# synergy-cart.net
KiCad netlist of a schematic drawn in EAGLE
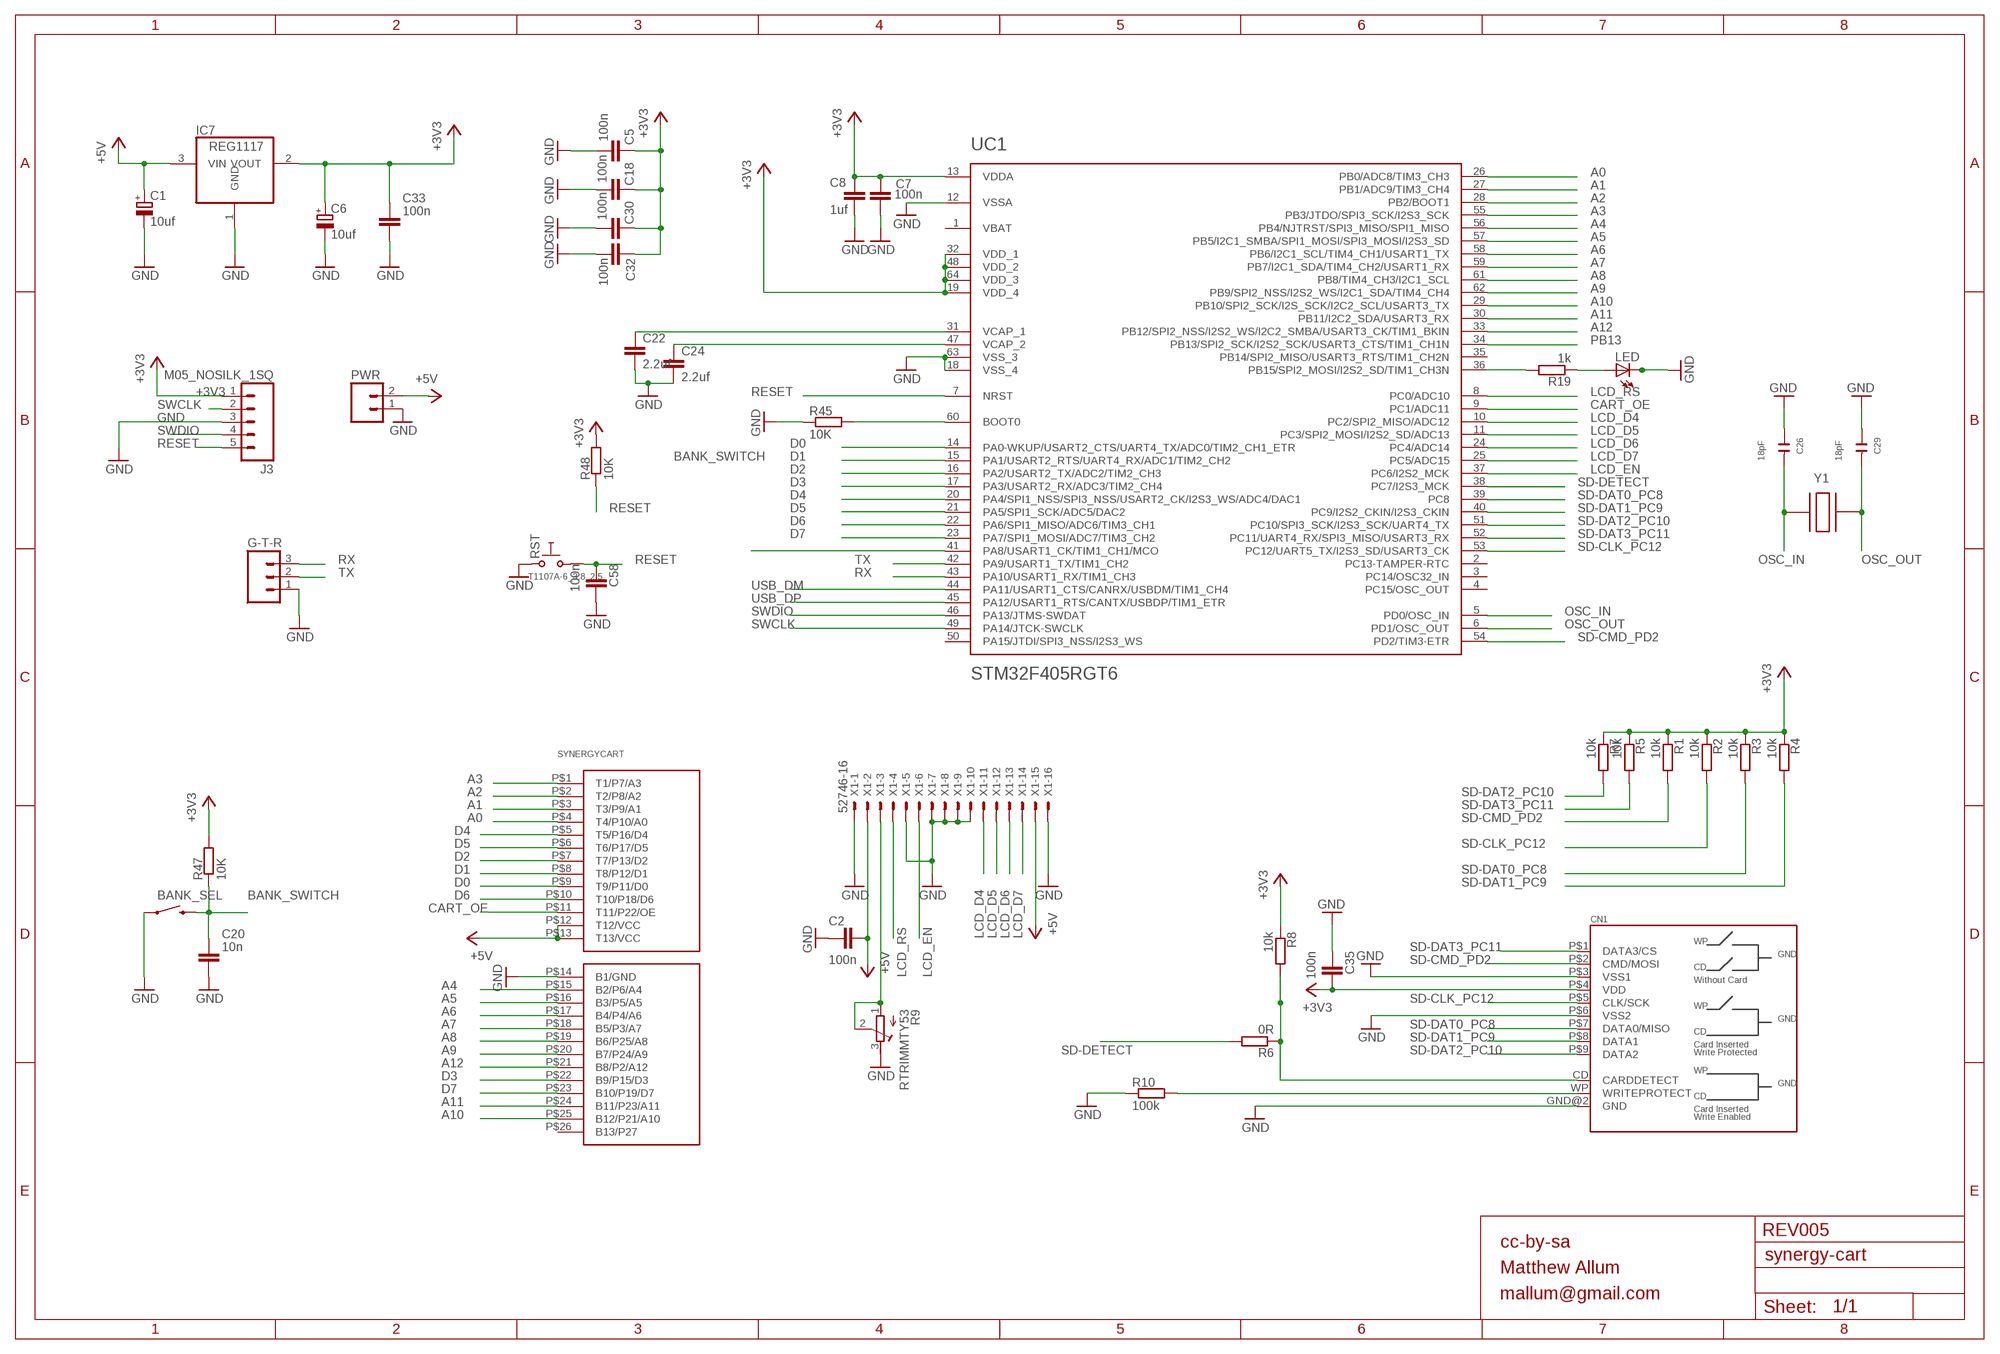
[diagram p0: schematic, sheet 1]

(export (version "E")
  (design (tool "Eeschema 10.0.6"))
  (components
    (comp (ref "BANK_SEL")
      (value "SWITCH-MOMENTARY-2PTH")
      (footprint "eagle-import:TACTILE-PTH")
      (libsource (lib "eagle-import") (part "SWITCH-MOMENTARY-2PTH"))
    )
    (comp (ref "C1")
      (value "10uf")
      (footprint "eagle-import:CT3216")
      (libsource (lib "eagle-import") (part "CAPACITOR_POLTANTALUM-CT3216"))
    )
    (comp (ref "C2")
      (value "100n")
      (footprint "eagle-import:C0603")
      (libsource (lib "eagle-import") (part "local_CAPACITOR0603"))
    )
    (comp (ref "C5")
      (value "100n")
      (footprint "eagle-import:C0603")
      (libsource (lib "eagle-import") (part "CAPACITOR0603"))
    )
    (comp (ref "C6")
      (value "10uf")
      (footprint "eagle-import:CT3216")
      (libsource (lib "eagle-import") (part "CAPACITOR_POLTANTALUM-CT3216"))
    )
    (comp (ref "C7")
      (value "100n")
      (footprint "eagle-import:C0603")
      (libsource (lib "eagle-import") (part "CAPACITOR0603"))
    )
    (comp (ref "C8")
      (value "1uf")
      (footprint "eagle-import:C0603")
      (libsource (lib "eagle-import") (part "CAPACITOR0603"))
    )
    (comp (ref "C18")
      (value "100n")
      (footprint "eagle-import:C0603")
      (libsource (lib "eagle-import") (part "CAPACITOR0603"))
    )
    (comp (ref "C20")
      (value "10n")
      (footprint "eagle-import:C0603")
      (libsource (lib "eagle-import") (part "CAPACITOR0603"))
    )
    (comp (ref "C22")
      (value "2.2uf")
      (footprint "eagle-import:C0805")
      (libsource (lib "eagle-import") (part "C-EUC0805"))
    )
    (comp (ref "C24")
      (value "2.2uf")
      (footprint "eagle-import:C0805")
      (libsource (lib "eagle-import") (part "C-EUC0805"))
    )
    (comp (ref "C26")
      (value "18pF")
      (footprint "eagle-import:C0603")
      (libsource (lib "eagle-import") (part "C-0603"))
    )
    (comp (ref "C29")
      (value "18pF")
      (footprint "eagle-import:C0603")
      (libsource (lib "eagle-import") (part "C-0603"))
    )
    (comp (ref "C30")
      (value "100n")
      (footprint "eagle-import:C0603")
      (libsource (lib "eagle-import") (part "CAPACITOR0603"))
    )
    (comp (ref "C32")
      (value "100n")
      (footprint "eagle-import:C0603")
      (libsource (lib "eagle-import") (part "CAPACITOR0603"))
    )
    (comp (ref "C33")
      (value "100n")
      (footprint "eagle-import:C0603")
      (libsource (lib "eagle-import") (part "CAPACITOR0603"))
    )
    (comp (ref "C35")
      (value "100n")
      (footprint "eagle-import:C0603")
      (libsource (lib "eagle-import") (part "local_CAPACITOR0603"))
    )
    (comp (ref "C58")
      (value "100n")
      (footprint "eagle-import:C0603")
      (libsource (lib "eagle-import") (part "local_CAPACITOR0603"))
    )
    (comp (ref "CN1")
      (value "SDCARD160611")
      (footprint "eagle-import:SDCARD_SMT_AMPH_160611")
      (libsource (lib "eagle-import") (part "SDCARD160611"))
    )
    (comp (ref "G-T-R")
      (value "M03PTH")
      (footprint "eagle-import:1X03")
      (libsource (lib "eagle-import") (part "M03PTH"))
    )
    (comp (ref "IC7")
      (value "REG1117")
      (footprint "eagle-import:SOT223")
      (libsource (lib "eagle-import") (part "REG1117"))
    )
    (comp (ref "J3")
      (value "M05_NOSILK_1SQ")
      (footprint "eagle-import:M05_NOSILK_1SQ")
      (libsource (lib "eagle-import") (part "M05_NOSILK_1SQ"))
    )
    (comp (ref "LED")
      (value "LEDCHIPLED_1206")
      (footprint "eagle-import:CHIPLED_1206")
      (libsource (lib "eagle-import") (part "LEDCHIPLED_1206"))
    )
    (comp (ref "PWR")
      (value "M02PTH")
      (footprint "eagle-import:1X02")
      (libsource (lib "eagle-import") (part "M02PTH"))
    )
    (comp (ref "R1")
      (value "10k")
      (footprint "eagle-import:R0603")
      (libsource (lib "eagle-import") (part "local_RESISTOR0603"))
    )
    (comp (ref "R2")
      (value "10k")
      (footprint "eagle-import:R0603")
      (libsource (lib "eagle-import") (part "local_RESISTOR0603"))
    )
    (comp (ref "R3")
      (value "10k")
      (footprint "eagle-import:R0603")
      (libsource (lib "eagle-import") (part "local_RESISTOR0603"))
    )
    (comp (ref "R4")
      (value "10k")
      (footprint "eagle-import:R0603")
      (libsource (lib "eagle-import") (part "local_RESISTOR0603"))
    )
    (comp (ref "R5")
      (value "10k")
      (footprint "eagle-import:R0603")
      (libsource (lib "eagle-import") (part "local_RESISTOR0603"))
    )
    (comp (ref "R6")
      (value "0R")
      (footprint "eagle-import:R0603")
      (libsource (lib "eagle-import") (part "local_RESISTOR0603"))
    )
    (comp (ref "R7")
      (value "10k")
      (footprint "eagle-import:R0603")
      (libsource (lib "eagle-import") (part "local_RESISTOR0603"))
    )
    (comp (ref "R8")
      (value "10k")
      (footprint "eagle-import:R0603")
      (libsource (lib "eagle-import") (part "local_RESISTOR0603"))
    )
    (comp (ref "R9")
      (value "RTRIMMTY53")
      (footprint "eagle-import:RTRIMTY53")
      (libsource (lib "eagle-import") (part "RTRIMMTY53"))
    )
    (comp (ref "R10")
      (value "100k")
      (footprint "eagle-import:R0603")
      (libsource (lib "eagle-import") (part "local_RESISTOR0603"))
    )
    (comp (ref "R19")
      (value "1k")
      (footprint "eagle-import:R0603")
      (libsource (lib "eagle-import") (part "local_RESISTOR0603"))
    )
    (comp (ref "R45")
      (value "10K")
      (footprint "eagle-import:R0603")
      (libsource (lib "eagle-import") (part "local_RESISTOR0603"))
    )
    (comp (ref "R47")
      (value "10K")
      (footprint "eagle-import:R0603")
      (libsource (lib "eagle-import") (part "RESISTOR0603"))
    )
    (comp (ref "R48")
      (value "10K")
      (footprint "eagle-import:R0603")
      (libsource (lib "eagle-import") (part "RESISTOR0603"))
    )
    (comp (ref "RST")
      (value "T1107A-6_3.8_2.5")
      (footprint "eagle-import:SW-TAKT_6X3.5_SMD")
      (libsource (lib "eagle-import") (part "SW-TAKT6"))
    )
    (comp (ref "SYNERGYCART")
      (value "SYNERGY_CARTSYNER")
      (footprint "eagle-import:SYNERGY_CART")
      (libsource (lib "eagle-import") (part "SYNERGY_CARTSYNER"))
    )
    (comp (ref "UC1")
      (value "STM32F405RGT6")
      (footprint "eagle-import:TQFP-10X10-64")
      (libsource (lib "eagle-import") (part "STM32F405RGT6"))
    )
    (comp (ref "X1")
      (value "52746-16")
      (footprint "eagle-import:52746-16")
      (libsource (lib "eagle-import") (part "52746-16"))
    )
    (comp (ref "Y1")
      (value "CRYSTAL-2")
      (footprint "eagle-import:CRYSTAL-SMD-5.0MM-3.2MM-2")
      (libsource (lib "eagle-import") (part "CRYSTAL-2"))
    )
  )
  (nets
    (net (code "1") (name "+3V3") (class "Default")
      (node (ref "C18") (pin "1") (pinfunction "1_1") (pintype "passive"))
      (node (ref "C30") (pin "1") (pinfunction "1_1") (pintype "passive"))
      (node (ref "C32") (pin "1") (pinfunction "1_1") (pintype "passive"))
      (node (ref "C33") (pin "1") (pinfunction "1_1") (pintype "passive"))
      (node (ref "C35") (pin "1") (pinfunction "1_1") (pintype "passive"))
      (node (ref "C5") (pin "1") (pinfunction "1_1") (pintype "passive"))
      (node (ref "C6") (pin "-") (pinfunction "+_-") (pintype "passive"))
      (node (ref "C7") (pin "1") (pinfunction "1_1") (pintype "passive"))
      (node (ref "C8") (pin "1") (pinfunction "1_1") (pintype "passive"))
      (node (ref "CN1") (pin "P$4") (pinfunction "VDD_P$4") (pintype "bidirectional"))
      (node (ref "IC7") (pin "2") (pinfunction "VOUT_2") (pintype "output"))
      (node (ref "J3") (pin "1") (pinfunction "1_1") (pintype "passive"))
      (node (ref "R1") (pin "1") (pinfunction "1_1") (pintype "passive"))
      (node (ref "R2") (pin "1") (pinfunction "1_1") (pintype "passive"))
      (node (ref "R3") (pin "1") (pinfunction "1_1") (pintype "passive"))
      (node (ref "R4") (pin "1") (pinfunction "1_1") (pintype "passive"))
      (node (ref "R47") (pin "2") (pinfunction "2_2") (pintype "passive"))
      (node (ref "R48") (pin "2") (pinfunction "2_2") (pintype "passive"))
      (node (ref "R5") (pin "1") (pinfunction "1_1") (pintype "passive"))
      (node (ref "R7") (pin "1") (pinfunction "1_1") (pintype "passive"))
      (node (ref "R8") (pin "1") (pinfunction "1_1") (pintype "passive"))
      (node (ref "UC1") (pin "13") (pinfunction "VDDA_13") (pintype "power_in"))
      (node (ref "UC1") (pin "19") (pinfunction "VDD_4_19") (pintype "power_in"))
      (node (ref "UC1") (pin "32") (pinfunction "VDD_1_32") (pintype "power_in"))
      (node (ref "UC1") (pin "48") (pinfunction "VDD_2_48") (pintype "power_in"))
      (node (ref "UC1") (pin "64") (pinfunction "VDD_3_64") (pintype "power_in"))
    )
    (net (code "2") (name "+5V") (class "Default")
      (node (ref "C1") (pin "-") (pinfunction "+_-") (pintype "passive"))
      (node (ref "C2") (pin "1") (pinfunction "1_1") (pintype "passive"))
      (node (ref "IC7") (pin "3") (pinfunction "VIN_3") (pintype "input"))
      (node (ref "PWR") (pin "2") (pinfunction "2_2") (pintype "passive"))
      (node (ref "SYNERGYCART") (pin "P$12") (pinfunction "T12/VCC_P$12") (pintype "bidirectional"))
      (node (ref "SYNERGYCART") (pin "P$13") (pinfunction "T13/VCC_P$13") (pintype "bidirectional"))
      (node (ref "X1") (pin "15") (pinfunction "S_15") (pintype "passive"))
      (node (ref "X1") (pin "2") (pinfunction "S_2") (pintype "passive"))
    )
    (net (code "3") (name "/A0") (class "Default")
      (node (ref "SYNERGYCART") (pin "P$4") (pinfunction "T4/P10/A0_P$4") (pintype "bidirectional"))
      (node (ref "UC1") (pin "26") (pinfunction "PB0/ADC8/TIM3_CH3_26") (pintype "bidirectional"))
    )
    (net (code "4") (name "/A1") (class "Default")
      (node (ref "SYNERGYCART") (pin "P$3") (pinfunction "T3/P9/A1_P$3") (pintype "bidirectional"))
      (node (ref "UC1") (pin "27") (pinfunction "PB1/ADC9/TIM3_CH4_27") (pintype "bidirectional"))
    )
    (net (code "5") (name "/A2") (class "Default")
      (node (ref "SYNERGYCART") (pin "P$2") (pinfunction "T2/P8/A2_P$2") (pintype "bidirectional"))
      (node (ref "UC1") (pin "28") (pinfunction "PB2/BOOT1_28") (pintype "bidirectional"))
    )
    (net (code "6") (name "/A3") (class "Default")
      (node (ref "SYNERGYCART") (pin "P$1") (pinfunction "T1/P7/A3_P$1") (pintype "bidirectional"))
      (node (ref "UC1") (pin "55") (pinfunction "PB3/JTDO/SPI3_SCK/I2S3_SCK_55") (pintype "bidirectional"))
    )
    (net (code "7") (name "/A4") (class "Default")
      (node (ref "SYNERGYCART") (pin "P$15") (pinfunction "B2/P6/A4_P$15") (pintype "bidirectional"))
      (node (ref "UC1") (pin "56") (pinfunction "PB4/NJTRST/SPI3_MISO/SPI1_MISO_56") (pintype "bidirectional"))
    )
    (net (code "8") (name "/A5") (class "Default")
      (node (ref "SYNERGYCART") (pin "P$16") (pinfunction "B3/P5/A5_P$16") (pintype "bidirectional"))
      (node (ref "UC1") (pin "57") (pinfunction "PB5/I2C1_SMBA/SPI1_MOSI/SPI3_MOSI/I2S3_SD_57") (pintype "bidirectional"))
    )
    (net (code "9") (name "/A6") (class "Default")
      (node (ref "SYNERGYCART") (pin "P$17") (pinfunction "B4/P4/A6_P$17") (pintype "bidirectional"))
      (node (ref "UC1") (pin "58") (pinfunction "PB6/I2C1_SCL/TIM4_CH1/USART1_TX_58") (pintype "bidirectional"))
    )
    (net (code "10") (name "/A7") (class "Default")
      (node (ref "SYNERGYCART") (pin "P$18") (pinfunction "B5/P3/A7_P$18") (pintype "bidirectional"))
      (node (ref "UC1") (pin "59") (pinfunction "PB7/I2C1_SDA/TIM4_CH2/USART1_RX_59") (pintype "bidirectional"))
    )
    (net (code "11") (name "/A8") (class "Default")
      (node (ref "SYNERGYCART") (pin "P$19") (pinfunction "B6/P25/A8_P$19") (pintype "bidirectional"))
      (node (ref "UC1") (pin "61") (pinfunction "PB8/TIM4_CH3/I2C1_SCL_61") (pintype "bidirectional"))
    )
    (net (code "12") (name "/A9") (class "Default")
      (node (ref "SYNERGYCART") (pin "P$20") (pinfunction "B7/P24/A9_P$20") (pintype "bidirectional"))
      (node (ref "UC1") (pin "62") (pinfunction "PB9/SPI2_NSS/I2S2_WS/I2C1_SDA/TIM4_CH4_62") (pintype "bidirectional"))
    )
    (net (code "13") (name "/A10") (class "Default")
      (node (ref "SYNERGYCART") (pin "P$25") (pinfunction "B12/P21/A10_P$25") (pintype "bidirectional"))
      (node (ref "UC1") (pin "29") (pinfunction "PB10/SPI2_SCK/I2S_SCK/I2C2_SCL/USART3_TX_29") (pintype "bidirectional"))
    )
    (net (code "14") (name "/A11") (class "Default")
      (node (ref "SYNERGYCART") (pin "P$24") (pinfunction "B11/P23/A11_P$24") (pintype "bidirectional"))
      (node (ref "UC1") (pin "30") (pinfunction "PB11/I2C2_SDA/USART3_RX_30") (pintype "bidirectional"))
    )
    (net (code "15") (name "/A12") (class "Default")
      (node (ref "SYNERGYCART") (pin "P$21") (pinfunction "B8/P2/A12_P$21") (pintype "bidirectional"))
      (node (ref "UC1") (pin "33") (pinfunction "PB12/SPI2_NSS/I2S2_WS/I2C2_SMBA/USART3_CK/TIM1_BKIN_33") (pintype "bidirectional"))
    )
    (net (code "16") (name "/BANK_SWITCH") (class "Default")
      (node (ref "BANK_SEL") (pin "3") (pinfunction "2_3") (pintype "passive"))
      (node (ref "C20") (pin "1") (pinfunction "1_1") (pintype "passive"))
      (node (ref "R47") (pin "1") (pinfunction "1_1") (pintype "passive"))
      (node (ref "UC1") (pin "41") (pinfunction "PA8/USART1_CK/TIM1_CH1/MCO_41") (pintype "bidirectional"))
    )
    (net (code "17") (name "/CART_OE") (class "Default")
      (node (ref "SYNERGYCART") (pin "P$11") (pinfunction "T11/P22/OE_P$11") (pintype "bidirectional"))
      (node (ref "UC1") (pin "9") (pinfunction "PC1/ADC11_9") (pintype "bidirectional"))
    )
    (net (code "18") (name "/D0") (class "Default")
      (node (ref "SYNERGYCART") (pin "P$9") (pinfunction "T9/P11/D0_P$9") (pintype "bidirectional"))
      (node (ref "UC1") (pin "14") (pinfunction "PA0-WKUP/USART2_CTS/UART4_TX/ADC0/TIM2_CH1_ETR_14") (pintype "bidirectional"))
    )
    (net (code "19") (name "/D1") (class "Default")
      (node (ref "SYNERGYCART") (pin "P$8") (pinfunction "T8/P12/D1_P$8") (pintype "bidirectional"))
      (node (ref "UC1") (pin "15") (pinfunction "PA1/USART2_RTS/UART4_RX/ADC1/TIM2_CH2_15") (pintype "bidirectional"))
    )
    (net (code "20") (name "/D2") (class "Default")
      (node (ref "SYNERGYCART") (pin "P$7") (pinfunction "T7/P13/D2_P$7") (pintype "bidirectional"))
      (node (ref "UC1") (pin "16") (pinfunction "PA2/USART2_TX/ADC2/TIM2_CH3_16") (pintype "bidirectional"))
    )
    (net (code "21") (name "/D3") (class "Default")
      (node (ref "SYNERGYCART") (pin "P$22") (pinfunction "B9/P15/D3_P$22") (pintype "bidirectional"))
      (node (ref "UC1") (pin "17") (pinfunction "PA3/USART2_RX/ADC3/TIM2_CH4_17") (pintype "bidirectional"))
    )
    (net (code "22") (name "/D4") (class "Default")
      (node (ref "SYNERGYCART") (pin "P$5") (pinfunction "T5/P16/D4_P$5") (pintype "bidirectional"))
      (node (ref "UC1") (pin "20") (pinfunction "PA4/SPI1_NSS/SPI3_NSS/USART2_CK/I2S3_WS/ADC4/DAC1_20") (pintype "bidirectional"))
    )
    (net (code "23") (name "/D5") (class "Default")
      (node (ref "SYNERGYCART") (pin "P$6") (pinfunction "T6/P17/D5_P$6") (pintype "bidirectional"))
      (node (ref "UC1") (pin "21") (pinfunction "PA5/SPI1_SCK/ADC5/DAC2_21") (pintype "bidirectional"))
    )
    (net (code "24") (name "/D6") (class "Default")
      (node (ref "SYNERGYCART") (pin "P$10") (pinfunction "T10/P18/D6_P$10") (pintype "bidirectional"))
      (node (ref "UC1") (pin "22") (pinfunction "PA6/SPI1_MISO/ADC6/TIM3_CH1_22") (pintype "bidirectional"))
    )
    (net (code "25") (name "/D7") (class "Default")
      (node (ref "SYNERGYCART") (pin "P$23") (pinfunction "B10/P19/D7_P$23") (pintype "bidirectional"))
      (node (ref "UC1") (pin "23") (pinfunction "PA7/SPI1_MOSI/ADC7/TIM3_CH2_23") (pintype "bidirectional"))
    )
    (net (code "26") (name "/LCD_D4") (class "Default")
      (node (ref "UC1") (pin "10") (pinfunction "PC2/SPI2_MISO/ADC12_10") (pintype "bidirectional"))
      (node (ref "X1") (pin "11") (pinfunction "S_11") (pintype "passive"))
    )
    (net (code "27") (name "/LCD_D5") (class "Default")
      (node (ref "UC1") (pin "11") (pinfunction "PC3/SPI2_MOSI/I2S2_SD/ADC13_11") (pintype "bidirectional"))
      (node (ref "X1") (pin "12") (pinfunction "S_12") (pintype "passive"))
    )
    (net (code "28") (name "/LCD_D6") (class "Default")
      (node (ref "UC1") (pin "24") (pinfunction "PC4/ADC14_24") (pintype "bidirectional"))
      (node (ref "X1") (pin "13") (pinfunction "S_13") (pintype "passive"))
    )
    (net (code "29") (name "/LCD_D7") (class "Default")
      (node (ref "UC1") (pin "25") (pinfunction "PC5/ADC15_25") (pintype "bidirectional"))
      (node (ref "X1") (pin "14") (pinfunction "S_14") (pintype "passive"))
    )
    (net (code "30") (name "/LCD_EN") (class "Default")
      (node (ref "UC1") (pin "37") (pinfunction "PC6/I2S2_MCK_37") (pintype "bidirectional"))
      (node (ref "X1") (pin "6") (pinfunction "S_6") (pintype "passive"))
    )
    (net (code "31") (name "/LCD_RS") (class "Default")
      (node (ref "UC1") (pin "8") (pinfunction "PC0/ADC10_8") (pintype "bidirectional"))
      (node (ref "X1") (pin "4") (pinfunction "S_4") (pintype "passive"))
    )
    (net (code "32") (name "/OSC_IN") (class "Default")
      (node (ref "C26") (pin "1") (pinfunction "1_1") (pintype "bidirectional"))
      (node (ref "UC1") (pin "5") (pinfunction "PD0/OSC_IN_5") (pintype "bidirectional"))
      (node (ref "Y1") (pin "2") (pinfunction "P$2_2") (pintype "bidirectional"))
    )
    (net (code "33") (name "/OSC_OUT") (class "Default")
      (node (ref "C29") (pin "1") (pinfunction "1_1") (pintype "bidirectional"))
      (node (ref "UC1") (pin "6") (pinfunction "PD1/OSC_OUT_6") (pintype "bidirectional"))
      (node (ref "Y1") (pin "1") (pinfunction "P$1_1") (pintype "bidirectional"))
    )
    (net (code "34") (name "/PB13") (class "Default")
      (node (ref "UC1") (pin "34") (pinfunction "PB13/SPI2_SCK/I2S2_SCK/USART3_CTS/TIM1_CH1N_34") (pintype "bidirectional"))
    )
    (net (code "35") (name "/RESET") (class "Default")
      (node (ref "C58") (pin "2") (pinfunction "2_2") (pintype "passive"))
      (node (ref "J3") (pin "5") (pinfunction "5_5") (pintype "passive"))
      (node (ref "R48") (pin "1") (pinfunction "1_1") (pintype "passive"))
      (node (ref "RST") (pin "P$2") (pinfunction "1_P$2") (pintype "passive"))
      (node (ref "UC1") (pin "7") (pinfunction "NRST_7") (pintype "bidirectional"))
    )
    (net (code "36") (name "/RX") (class "Default")
      (node (ref "G-T-R") (pin "3") (pinfunction "3_3") (pintype "passive"))
      (node (ref "UC1") (pin "43") (pinfunction "PA10/USART1_RX/TIM1_CH3_43") (pintype "bidirectional"))
    )
    (net (code "37") (name "/SD-CLK_PC12") (class "Default")
      (node (ref "CN1") (pin "P$5") (pinfunction "CLK/SCK_P$5") (pintype "bidirectional"))
      (node (ref "R2") (pin "2") (pinfunction "2_2") (pintype "passive"))
      (node (ref "UC1") (pin "53") (pinfunction "PC12/UART5_TX/I2S3_SD/USART3_CK_53") (pintype "bidirectional"))
    )
    (net (code "38") (name "/SD-CMD_PD2") (class "Default")
      (node (ref "CN1") (pin "P$2") (pinfunction "CMD/MOSI_P$2") (pintype "bidirectional"))
      (node (ref "R1") (pin "2") (pinfunction "2_2") (pintype "passive"))
      (node (ref "UC1") (pin "54") (pinfunction "PD2/TIM3-ETR_54") (pintype "bidirectional"))
    )
    (net (code "39") (name "/SD-DAT0_PC8") (class "Default")
      (node (ref "CN1") (pin "P$7") (pinfunction "DATA0/MISO_P$7") (pintype "bidirectional"))
      (node (ref "R3") (pin "2") (pinfunction "2_2") (pintype "passive"))
      (node (ref "UC1") (pin "39") (pinfunction "PC8_39") (pintype "bidirectional"))
    )
    (net (code "40") (name "/SD-DAT1_PC9") (class "Default")
      (node (ref "CN1") (pin "P$8") (pinfunction "DATA1_P$8") (pintype "bidirectional"))
      (node (ref "R4") (pin "2") (pinfunction "2_2") (pintype "passive"))
      (node (ref "UC1") (pin "40") (pinfunction "PC9/I2S2_CKIN/I2S3_CKIN_40") (pintype "bidirectional"))
    )
    (net (code "41") (name "/SD-DAT2_PC10") (class "Default")
      (node (ref "CN1") (pin "P$9") (pinfunction "DATA2_P$9") (pintype "bidirectional"))
      (node (ref "R7") (pin "2") (pinfunction "2_2") (pintype "passive"))
      (node (ref "UC1") (pin "51") (pinfunction "PC10/SPI3_SCK/I2S3_SCK/UART4_TX_51") (pintype "bidirectional"))
    )
    (net (code "42") (name "/SD-DAT3_PC11") (class "Default")
      (node (ref "CN1") (pin "P$1") (pinfunction "DATA3/CS_P$1") (pintype "bidirectional"))
      (node (ref "R5") (pin "2") (pinfunction "2_2") (pintype "passive"))
      (node (ref "UC1") (pin "52") (pinfunction "PC11/UART4_RX/SPI3_MISO/USART3_RX_52") (pintype "bidirectional"))
    )
    (net (code "43") (name "/SD-DETECT") (class "Default")
      (node (ref "R6") (pin "2") (pinfunction "2_2") (pintype "passive"))
      (node (ref "UC1") (pin "38") (pinfunction "PC7/I2S3_MCK_38") (pintype "bidirectional"))
    )
    (net (code "44") (name "/SWCLK") (class "Default")
      (node (ref "J3") (pin "2") (pinfunction "2_2") (pintype "passive"))
      (node (ref "UC1") (pin "49") (pinfunction "PA14/JTCK-SWCLK_49") (pintype "bidirectional"))
    )
    (net (code "45") (name "/SWDIO") (class "Default")
      (node (ref "J3") (pin "4") (pinfunction "4_4") (pintype "passive"))
      (node (ref "UC1") (pin "46") (pinfunction "PA13/JTMS-SWDAT_46") (pintype "bidirectional"))
    )
    (net (code "46") (name "/TX") (class "Default")
      (node (ref "G-T-R") (pin "2") (pinfunction "2_2") (pintype "passive"))
      (node (ref "UC1") (pin "42") (pinfunction "PA9/USART1_TX/TIM1_CH2_42") (pintype "bidirectional"))
    )
    (net (code "47") (name "/USB_DM") (class "Default")
      (node (ref "UC1") (pin "44") (pinfunction "PA11/USART1_CTS/CANRX/USBDM/TIM1_CH4_44") (pintype "bidirectional"))
    )
    (net (code "48") (name "/USB_DP") (class "Default")
      (node (ref "UC1") (pin "45") (pinfunction "PA12/USART1_RTS/CANTX/USBDP/TIM1_ETR_45") (pintype "bidirectional"))
    )
    (net (code "49") (name "/VBAT") (class "Default")
      (node (ref "UC1") (pin "1") (pinfunction "VBAT_1") (pintype "power_in"))
    )
    (net (code "50") (name "GND") (class "Default")
      (node (ref "BANK_SEL") (pin "1") (pinfunction "1_1") (pintype "passive"))
      (node (ref "C1") (pin "+") (pinfunction "-_+") (pintype "passive"))
      (node (ref "C18") (pin "2") (pinfunction "2_2") (pintype "passive"))
      (node (ref "C2") (pin "2") (pinfunction "2_2") (pintype "passive"))
      (node (ref "C20") (pin "2") (pinfunction "2_2") (pintype "passive"))
      (node (ref "C22") (pin "2") (pinfunction "2_2") (pintype "passive"))
      (node (ref "C24") (pin "2") (pinfunction "2_2") (pintype "passive"))
      (node (ref "C26") (pin "2") (pinfunction "2_2") (pintype "bidirectional"))
      (node (ref "C29") (pin "2") (pinfunction "2_2") (pintype "bidirectional"))
      (node (ref "C30") (pin "2") (pinfunction "2_2") (pintype "passive"))
      (node (ref "C32") (pin "2") (pinfunction "2_2") (pintype "passive"))
      (node (ref "C33") (pin "2") (pinfunction "2_2") (pintype "passive"))
      (node (ref "C35") (pin "2") (pinfunction "2_2") (pintype "passive"))
      (node (ref "C5") (pin "2") (pinfunction "2_2") (pintype "passive"))
      (node (ref "C58") (pin "1") (pinfunction "1_1") (pintype "passive"))
      (node (ref "C6") (pin "+") (pinfunction "-_+") (pintype "passive"))
      (node (ref "C7") (pin "2") (pinfunction "2_2") (pintype "passive"))
      (node (ref "C8") (pin "2") (pinfunction "2_2") (pintype "passive"))
      (node (ref "CN1") (pin "GND@2") (pinfunction "GND_GND@2") (pintype "bidirectional"))
      (node (ref "CN1") (pin "P$3") (pinfunction "VSS1_P$3") (pintype "bidirectional"))
      (node (ref "CN1") (pin "P$6") (pinfunction "VSS2_P$6") (pintype "bidirectional"))
      (node (ref "G-T-R") (pin "1") (pinfunction "1_1") (pintype "passive"))
      (node (ref "IC7") (pin "1") (pinfunction "GND_1") (pintype "power_in"))
      (node (ref "J3") (pin "3") (pinfunction "3_3") (pintype "passive"))
      (node (ref "LED") (pin "C") (pinfunction "C_C") (pintype "passive"))
      (node (ref "PWR") (pin "1") (pinfunction "1_1") (pintype "passive"))
      (node (ref "R10") (pin "1") (pinfunction "1_1") (pintype "passive"))
      (node (ref "R45") (pin "1") (pinfunction "1_1") (pintype "passive"))
      (node (ref "R9") (pin "3") (pinfunction "E_3") (pintype "passive"))
      (node (ref "RST") (pin "P$1") (pinfunction "0_P$1") (pintype "passive"))
      (node (ref "SYNERGYCART") (pin "P$14") (pinfunction "B1/GND_P$14") (pintype "bidirectional"))
      (node (ref "UC1") (pin "12") (pinfunction "VSSA_12") (pintype "power_in"))
      (node (ref "UC1") (pin "18") (pinfunction "VSS_4_18") (pintype "power_in"))
      (node (ref "UC1") (pin "63") (pinfunction "VSS_3_63") (pintype "power_in"))
      (node (ref "X1") (pin "1") (pinfunction "S_1") (pintype "passive"))
      (node (ref "X1") (pin "10") (pinfunction "S_10") (pintype "passive"))
      (node (ref "X1") (pin "16") (pinfunction "S_16") (pintype "passive"))
      (node (ref "X1") (pin "5") (pinfunction "S_5") (pintype "passive"))
      (node (ref "X1") (pin "7") (pinfunction "S_7") (pintype "passive"))
      (node (ref "X1") (pin "8") (pinfunction "S_8") (pintype "passive"))
      (node (ref "X1") (pin "9") (pinfunction "S_9") (pintype "passive"))
    )
    (net (code "51") (name "Net-(CN1-CARDDETECT)") (class "Default")
      (node (ref "CN1") (pin "CD") (pinfunction "CARDDETECT_CD") (pintype "bidirectional"))
      (node (ref "R6") (pin "1") (pinfunction "1_1") (pintype "passive"))
      (node (ref "R8") (pin "2") (pinfunction "2_2") (pintype "passive"))
    )
    (net (code "52") (name "Net-(CN1-WRITEPROTECT)") (class "Default")
      (node (ref "CN1") (pin "WP") (pinfunction "WRITEPROTECT_WP") (pintype "bidirectional"))
      (node (ref "R10") (pin "2") (pinfunction "2_2") (pintype "passive"))
    )
    (net (code "53") (name "Net-(LED-PadA)") (class "Default")
      (node (ref "LED") (pin "A") (pinfunction "A_A") (pintype "passive"))
      (node (ref "R19") (pin "1") (pinfunction "1_1") (pintype "passive"))
    )
    (net (code "54") (name "Net-(R9-A)") (class "Default")
      (node (ref "R9") (pin "1") (pinfunction "A_1") (pintype "passive"))
      (node (ref "R9") (pin "2") (pinfunction "S_2") (pintype "passive"))
      (node (ref "X1") (pin "3") (pinfunction "S_3") (pintype "passive"))
    )
    (net (code "55") (name "Net-(UC1-BOOT0)") (class "Default")
      (node (ref "R45") (pin "2") (pinfunction "2_2") (pintype "passive"))
      (node (ref "UC1") (pin "60") (pinfunction "BOOT0_60") (pintype "bidirectional"))
    )
    (net (code "56") (name "Net-(UC1-PB15{slash}SPI2_MOSI{slash}I2S2_SD{slash}TIM1_CH3N)") (class "Default")
      (node (ref "R19") (pin "2") (pinfunction "2_2") (pintype "passive"))
      (node (ref "UC1") (pin "36") (pinfunction "PB15/SPI2_MOSI/I2S2_SD/TIM1_CH3N_36") (pintype "bidirectional"))
    )
    (net (code "57") (name "Net-(UC1-VCAP_1)") (class "Default")
      (node (ref "C22") (pin "1") (pinfunction "1_1") (pintype "passive"))
      (node (ref "UC1") (pin "31") (pinfunction "VCAP_1_31") (pintype "power_in"))
    )
    (net (code "58") (name "Net-(UC1-VCAP_2)") (class "Default")
      (node (ref "C24") (pin "1") (pinfunction "1_1") (pintype "passive"))
      (node (ref "UC1") (pin "47") (pinfunction "VCAP_2_47") (pintype "power_in"))
    )
    (net (code "59") (name "unconnected-(SYNERGYCART-B13{slash}P27-PadP$26)") (class "Default")
      (node (ref "SYNERGYCART") (pin "P$26") (pinfunction "B13/P27_P$26") (pintype "bidirectional"))
    )
    (net (code "60") (name "unconnected-(UC1-PA15{slash}JTDI{slash}SPI3_NSS{slash}I2S3_WS-Pad50)") (class "Default")
      (node (ref "UC1") (pin "50") (pinfunction "PA15/JTDI/SPI3_NSS/I2S3_WS_50") (pintype "bidirectional"))
    )
    (net (code "61") (name "unconnected-(UC1-PB14{slash}SPI2_MISO{slash}USART3_RTS{slash}TIM1_CH2N-Pad35)") (class "Default")
      (node (ref "UC1") (pin "35") (pinfunction "PB14/SPI2_MISO/USART3_RTS/TIM1_CH2N_35") (pintype "bidirectional"))
    )
    (net (code "62") (name "unconnected-(UC1-PC13-TAMPER-RTC-Pad2)") (class "Default")
      (node (ref "UC1") (pin "2") (pinfunction "PC13-TAMPER-RTC_2") (pintype "bidirectional"))
    )
    (net (code "63") (name "unconnected-(UC1-PC14{slash}OSC32_IN-Pad3)") (class "Default")
      (node (ref "UC1") (pin "3") (pinfunction "PC14/OSC32_IN_3") (pintype "bidirectional"))
    )
    (net (code "64") (name "unconnected-(UC1-PC15{slash}OSC_OUT-Pad4)") (class "Default")
      (node (ref "UC1") (pin "4") (pinfunction "PC15/OSC_OUT_4") (pintype "bidirectional"))
    )
  )
)
